# textdisplay.net
KiCad netlist of a schematic drawn in EAGLE
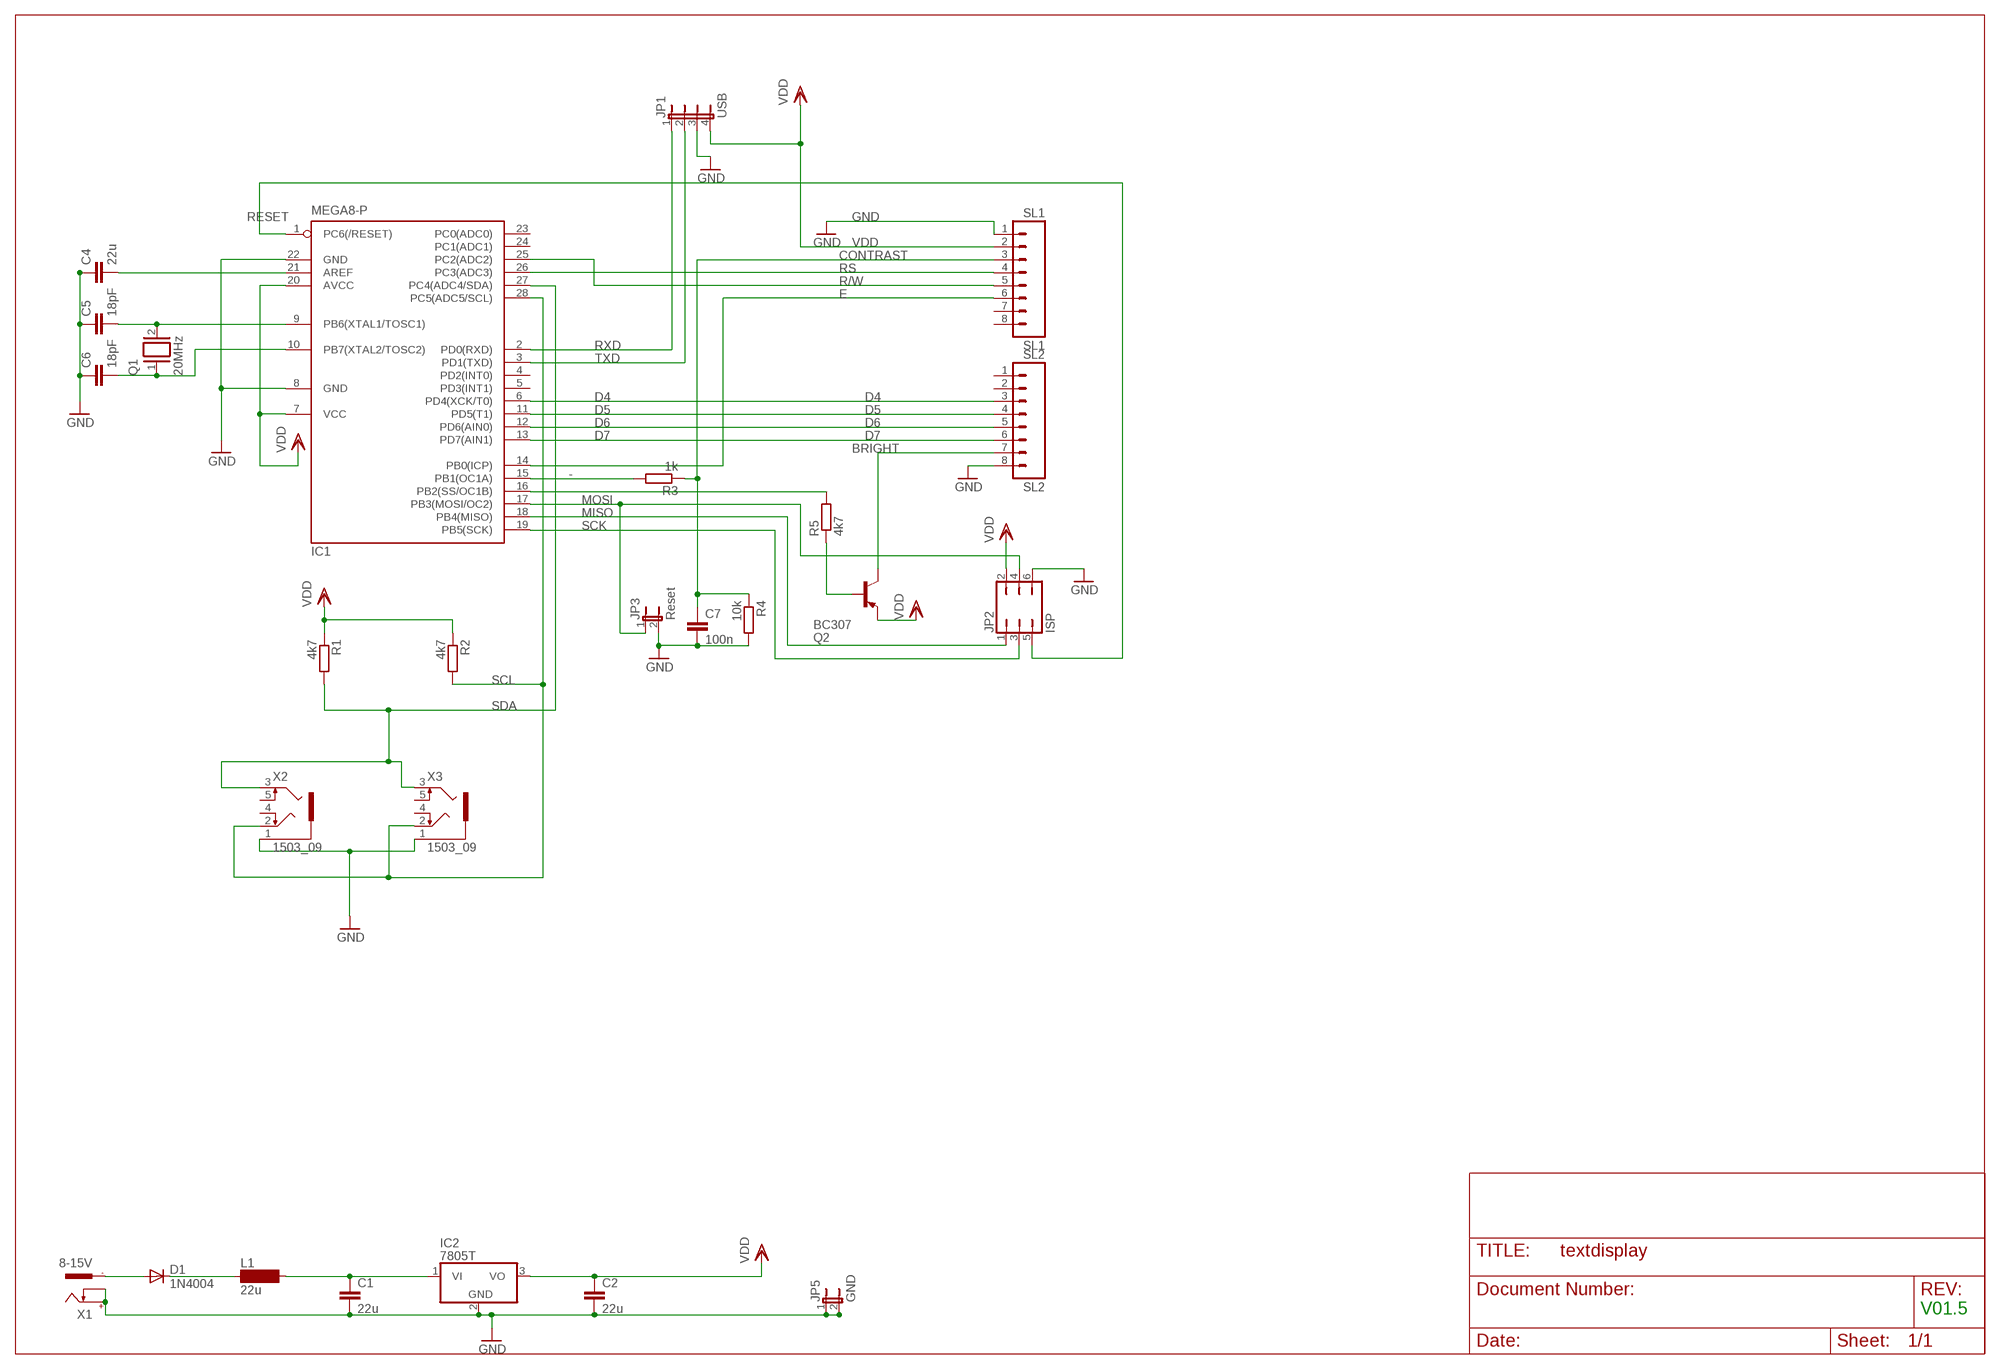
[diagram p0: schematic, sheet 1]

(export (version "E")
  (design (tool "Eeschema 10.0.6"))
  (components
    (comp (ref "C1")
      (value "22u")
      (footprint "eagle-import:C1206")
      (libsource (lib "eagle-import") (part "C-EUC1206"))
    )
    (comp (ref "C2")
      (value "22u")
      (footprint "eagle-import:C1206")
      (libsource (lib "eagle-import") (part "C-EUC1206"))
    )
    (comp (ref "C4")
      (value "22u")
      (footprint "eagle-import:C1206")
      (libsource (lib "eagle-import") (part "C-EUC1206"))
    )
    (comp (ref "C5")
      (value "18pF")
      (footprint "eagle-import:C025-025X050")
      (libsource (lib "eagle-import") (part "C-EU025-025X050"))
    )
    (comp (ref "C6")
      (value "18pF")
      (footprint "eagle-import:C025-025X050")
      (libsource (lib "eagle-import") (part "C-EU025-025X050"))
    )
    (comp (ref "C7")
      (value "100n")
      (footprint "eagle-import:C050-025X075")
      (libsource (lib "eagle-import") (part "C-EU050-025X075"))
    )
    (comp (ref "D1")
      (value "1N4004")
      (footprint "eagle-import:DO41-10")
      (libsource (lib "eagle-import") (part "1N4004"))
    )
    (comp (ref "IC1")
      (value "MEGA8-P")
      (footprint "eagle-import:DIL28-3")
      (libsource (lib "eagle-import") (part "MEGA8-P"))
    )
    (comp (ref "IC2")
      (value "7805T")
      (footprint "eagle-import:TO220H")
      (libsource (lib "eagle-import") (part "78T05"))
    )
    (comp (ref "JP1")
      (value "USB")
      (footprint "eagle-import:JP4")
      (libsource (lib "eagle-import") (part "JP4E"))
    )
    (comp (ref "JP2")
      (value "ISP")
      (footprint "eagle-import:JP3Q")
      (libsource (lib "eagle-import") (part "JP3Q"))
    )
    (comp (ref "JP3")
      (value "Reset")
      (footprint "eagle-import:JP1")
      (libsource (lib "eagle-import") (part "JP1E"))
    )
    (comp (ref "JP5")
      (value "GND")
      (footprint "eagle-import:JP1")
      (libsource (lib "eagle-import") (part "JP1E"))
    )
    (comp (ref "L1")
      (value "22u")
      (footprint "eagle-import:MS85")
      (libsource (lib "eagle-import") (part "MS85"))
    )
    (comp (ref "Q1")
      (value "20MHz")
      (footprint "eagle-import:QS")
      (libsource (lib "eagle-import") (part "XTAL/S"))
    )
    (comp (ref "Q2")
      (value "BC307")
      (footprint "eagle-import:TO92")
      (libsource (lib "eagle-import") (part "BC307"))
    )
    (comp (ref "R1")
      (value "4k7")
      (footprint "eagle-import:0207_2V")
      (libsource (lib "eagle-import") (part "R-EU_0207/2V"))
    )
    (comp (ref "R2")
      (value "4k7")
      (footprint "eagle-import:0207_2V")
      (libsource (lib "eagle-import") (part "R-EU_0207/2V"))
    )
    (comp (ref "R3")
      (value "1k")
      (footprint "eagle-import:0207_2V")
      (libsource (lib "eagle-import") (part "R-EU_0207/2V"))
    )
    (comp (ref "R4")
      (value "10k")
      (footprint "eagle-import:0207_2V")
      (libsource (lib "eagle-import") (part "R-EU_0207/2V"))
    )
    (comp (ref "R5")
      (value "4k7")
      (footprint "eagle-import:0207_2V")
      (libsource (lib "eagle-import") (part "R-EU_0207/2V"))
    )
    (comp (ref "SL1")
      (value "SL1")
      (footprint "eagle-import:08P")
      (libsource (lib "eagle-import") (part "M08"))
    )
    (comp (ref "SL2")
      (value "SL2")
      (footprint "eagle-import:08P")
      (libsource (lib "eagle-import") (part "M08"))
    )
    (comp (ref "X1")
      (value "8-15V")
      (footprint "eagle-import:737992-5")
      (libsource (lib "eagle-import") (part "737992-55"))
    )
    (comp (ref "X2")
      (value "1503_09")
      (footprint "eagle-import:1503_09")
      (libsource (lib "eagle-import") (part "1503_09"))
    )
    (comp (ref "X3")
      (value "1503_09")
      (footprint "eagle-import:1503_09")
      (libsource (lib "eagle-import") (part "1503_09"))
    )
  )
  (nets
    (net (code "1") (name "/-") (class "Default")
      (node (ref "IC1") (pin "15") (pinfunction "PB1(OC1A)_15") (pintype "bidirectional"))
      (node (ref "R3") (pin "2") (pinfunction "2_2") (pintype "passive"))
    )
    (net (code "2") (name "/BRIGHT") (class "Default")
      (node (ref "Q2") (pin "3") (pinfunction "C_3") (pintype "passive"))
      (node (ref "SL2") (pin "7") (pinfunction "7_7") (pintype "passive"))
    )
    (net (code "3") (name "/CONTRAST") (class "Default")
      (node (ref "C7") (pin "1") (pinfunction "1_1") (pintype "passive"))
      (node (ref "R3") (pin "1") (pinfunction "1_1") (pintype "passive"))
      (node (ref "R4") (pin "1") (pinfunction "1_1") (pintype "passive"))
      (node (ref "SL1") (pin "3") (pinfunction "3_3") (pintype "passive"))
    )
    (net (code "4") (name "/D4") (class "Default")
      (node (ref "IC1") (pin "6") (pinfunction "PD4(XCK/T0)_6") (pintype "bidirectional"))
      (node (ref "SL2") (pin "3") (pinfunction "3_3") (pintype "passive"))
    )
    (net (code "5") (name "/D5") (class "Default")
      (node (ref "IC1") (pin "11") (pinfunction "PD5(T1)_11") (pintype "bidirectional"))
      (node (ref "SL2") (pin "4") (pinfunction "4_4") (pintype "passive"))
    )
    (net (code "6") (name "/D6") (class "Default")
      (node (ref "IC1") (pin "12") (pinfunction "PD6(AIN0)_12") (pintype "bidirectional"))
      (node (ref "SL2") (pin "5") (pinfunction "5_5") (pintype "passive"))
    )
    (net (code "7") (name "/D7") (class "Default")
      (node (ref "IC1") (pin "13") (pinfunction "PD7(AIN1)_13") (pintype "bidirectional"))
      (node (ref "SL2") (pin "6") (pinfunction "6_6") (pintype "passive"))
    )
    (net (code "8") (name "/E") (class "Default")
      (node (ref "IC1") (pin "14") (pinfunction "PB0(ICP)_14") (pintype "bidirectional"))
      (node (ref "SL1") (pin "6") (pinfunction "6_6") (pintype "passive"))
    )
    (net (code "9") (name "/MISO") (class "Default")
      (node (ref "IC1") (pin "18") (pinfunction "PB4(MISO)_18") (pintype "bidirectional"))
      (node (ref "JP2") (pin "1") (pinfunction "1_1") (pintype "passive"))
    )
    (net (code "10") (name "/MOSI") (class "Default")
      (node (ref "IC1") (pin "17") (pinfunction "PB3(MOSI/OC2)_17") (pintype "bidirectional"))
      (node (ref "JP2") (pin "4") (pinfunction "4_4") (pintype "passive"))
      (node (ref "JP3") (pin "1") (pinfunction "1_1") (pintype "passive"))
    )
    (net (code "11") (name "/RESET") (class "Default")
      (node (ref "IC1") (pin "1") (pinfunction "PC6(/RESET)_1") (pintype "bidirectional"))
      (node (ref "JP2") (pin "5") (pinfunction "5_5") (pintype "passive"))
    )
    (net (code "12") (name "/RS") (class "Default")
      (node (ref "IC1") (pin "26") (pinfunction "PC3(ADC3)_26") (pintype "bidirectional"))
      (node (ref "SL1") (pin "4") (pinfunction "4_4") (pintype "passive"))
    )
    (net (code "13") (name "/RXD") (class "Default")
      (node (ref "IC1") (pin "2") (pinfunction "PD0(RXD)_2") (pintype "bidirectional"))
      (node (ref "JP1") (pin "1") (pinfunction "1_1") (pintype "passive"))
    )
    (net (code "14") (name "/R{slash}W") (class "Default")
      (node (ref "IC1") (pin "25") (pinfunction "PC2(ADC2)_25") (pintype "bidirectional"))
      (node (ref "SL1") (pin "5") (pinfunction "5_5") (pintype "passive"))
    )
    (net (code "15") (name "/SCK") (class "Default")
      (node (ref "IC1") (pin "19") (pinfunction "PB5(SCK)_19") (pintype "bidirectional"))
      (node (ref "JP2") (pin "3") (pinfunction "3_3") (pintype "passive"))
    )
    (net (code "16") (name "/SCL") (class "Default")
      (node (ref "IC1") (pin "28") (pinfunction "PC5(ADC5/SCL)_28") (pintype "bidirectional"))
      (node (ref "R2") (pin "2") (pinfunction "2_2") (pintype "passive"))
      (node (ref "X2") (pin "2") (pinfunction "2_2") (pintype "passive"))
      (node (ref "X3") (pin "2") (pinfunction "2_2") (pintype "passive"))
    )
    (net (code "17") (name "/SDA") (class "Default")
      (node (ref "IC1") (pin "27") (pinfunction "PC4(ADC4/SDA)_27") (pintype "bidirectional"))
      (node (ref "R1") (pin "2") (pinfunction "2_2") (pintype "passive"))
      (node (ref "X2") (pin "3") (pinfunction "3_3") (pintype "passive"))
      (node (ref "X3") (pin "3") (pinfunction "3_3") (pintype "passive"))
    )
    (net (code "18") (name "/TXD") (class "Default")
      (node (ref "IC1") (pin "3") (pinfunction "PD1(TXD)_3") (pintype "bidirectional"))
      (node (ref "JP1") (pin "2") (pinfunction "2_2") (pintype "passive"))
    )
    (net (code "19") (name "GND") (class "Default")
      (node (ref "C1") (pin "2") (pinfunction "2_2") (pintype "passive"))
      (node (ref "C2") (pin "2") (pinfunction "2_2") (pintype "passive"))
      (node (ref "C4") (pin "1") (pinfunction "1_1") (pintype "passive"))
      (node (ref "C5") (pin "1") (pinfunction "1_1") (pintype "passive"))
      (node (ref "C6") (pin "1") (pinfunction "1_1") (pintype "passive"))
      (node (ref "C7") (pin "2") (pinfunction "2_2") (pintype "passive"))
      (node (ref "IC1") (pin "22") (pinfunction "GND_22") (pintype "power_in"))
      (node (ref "IC1") (pin "8") (pinfunction "GND_8") (pintype "power_in"))
      (node (ref "IC2") (pin "2") (pinfunction "GND_2") (pintype "passive"))
      (node (ref "JP1") (pin "3") (pinfunction "3_3") (pintype "passive"))
      (node (ref "JP2") (pin "6") (pinfunction "6_6") (pintype "passive"))
      (node (ref "JP3") (pin "2") (pinfunction "2_2") (pintype "passive"))
      (node (ref "JP5") (pin "1") (pinfunction "1_1") (pintype "passive"))
      (node (ref "JP5") (pin "2") (pinfunction "2_2") (pintype "passive"))
      (node (ref "R4") (pin "2") (pinfunction "2_2") (pintype "passive"))
      (node (ref "SL1") (pin "1") (pinfunction "1_1") (pintype "passive"))
      (node (ref "SL2") (pin "8") (pinfunction "8_8") (pintype "passive"))
      (node (ref "X1") (pin "+") (pinfunction "+_+") (pintype "passive"))
      (node (ref "X1") (pin "K") (pinfunction "K_K") (pintype "passive"))
      (node (ref "X2") (pin "1") (pinfunction "1_1") (pintype "passive"))
      (node (ref "X3") (pin "1") (pinfunction "1_1") (pintype "passive"))
    )
    (net (code "20") (name "Net-(D1-PadA)") (class "Default")
      (node (ref "D1") (pin "A") (pinfunction "A_A") (pintype "passive"))
      (node (ref "X1") (pin "-1") (pinfunction "-1_-1") (pintype "passive"))
    )
    (net (code "21") (name "Net-(D1-PadC)") (class "Default")
      (node (ref "D1") (pin "C") (pinfunction "C_C") (pintype "passive"))
      (node (ref "L1") (pin "1") (pinfunction "1_1") (pintype "passive"))
    )
    (net (code "22") (name "Net-(IC1-AREF)") (class "Default")
      (node (ref "C4") (pin "2") (pinfunction "2_2") (pintype "passive"))
      (node (ref "IC1") (pin "21") (pinfunction "AREF_21") (pintype "passive"))
    )
    (net (code "23") (name "Net-(IC1-PB2(SS{slash}OC1B))") (class "Default")
      (node (ref "IC1") (pin "16") (pinfunction "PB2(SS/OC1B)_16") (pintype "bidirectional"))
      (node (ref "R5") (pin "2") (pinfunction "2_2") (pintype "passive"))
    )
    (net (code "24") (name "Net-(IC1-PB6(XTAL1{slash}TOSC1))") (class "Default")
      (node (ref "C5") (pin "2") (pinfunction "2_2") (pintype "passive"))
      (node (ref "IC1") (pin "9") (pinfunction "PB6(XTAL1/TOSC1)_9") (pintype "bidirectional"))
      (node (ref "Q1") (pin "2") (pinfunction "2_2") (pintype "passive"))
    )
    (net (code "25") (name "Net-(IC1-PB7(XTAL2{slash}TOSC2))") (class "Default")
      (node (ref "C6") (pin "2") (pinfunction "2_2") (pintype "passive"))
      (node (ref "IC1") (pin "10") (pinfunction "PB7(XTAL2/TOSC2)_10") (pintype "bidirectional"))
      (node (ref "Q1") (pin "1") (pinfunction "1_1") (pintype "passive"))
    )
    (net (code "26") (name "Net-(IC2-VI)") (class "Default")
      (node (ref "C1") (pin "1") (pinfunction "1_1") (pintype "passive"))
      (node (ref "IC2") (pin "1") (pinfunction "VI_1") (pintype "input"))
      (node (ref "L1") (pin "2") (pinfunction "2_2") (pintype "passive"))
    )
    (net (code "27") (name "Net-(Q2-B)") (class "Default")
      (node (ref "Q2") (pin "2") (pinfunction "B_2") (pintype "passive"))
      (node (ref "R5") (pin "1") (pinfunction "1_1") (pintype "passive"))
    )
    (net (code "28") (name "VDD") (class "Default")
      (node (ref "C2") (pin "1") (pinfunction "1_1") (pintype "passive"))
      (node (ref "IC1") (pin "20") (pinfunction "AVCC_20") (pintype "power_in"))
      (node (ref "IC1") (pin "7") (pinfunction "VCC_7") (pintype "power_in"))
      (node (ref "IC2") (pin "3") (pinfunction "VO_3") (pintype "passive"))
      (node (ref "JP1") (pin "4") (pinfunction "4_4") (pintype "passive"))
      (node (ref "JP2") (pin "2") (pinfunction "2_2") (pintype "passive"))
      (node (ref "Q2") (pin "1") (pinfunction "E_1") (pintype "passive"))
      (node (ref "R1") (pin "1") (pinfunction "1_1") (pintype "passive"))
      (node (ref "R2") (pin "1") (pinfunction "1_1") (pintype "passive"))
      (node (ref "SL1") (pin "2") (pinfunction "2_2") (pintype "passive"))
    )
    (net (code "29") (name "unconnected-(IC1-PC0(ADC0)-Pad23)") (class "Default")
      (node (ref "IC1") (pin "23") (pinfunction "PC0(ADC0)_23") (pintype "bidirectional"))
    )
    (net (code "30") (name "unconnected-(IC1-PC1(ADC1)-Pad24)") (class "Default")
      (node (ref "IC1") (pin "24") (pinfunction "PC1(ADC1)_24") (pintype "bidirectional"))
    )
    (net (code "31") (name "unconnected-(IC1-PD2(INT0)-Pad4)") (class "Default")
      (node (ref "IC1") (pin "4") (pinfunction "PD2(INT0)_4") (pintype "bidirectional"))
    )
    (net (code "32") (name "unconnected-(IC1-PD3(INT1)-Pad5)") (class "Default")
      (node (ref "IC1") (pin "5") (pinfunction "PD3(INT1)_5") (pintype "bidirectional"))
    )
    (net (code "33") (name "unconnected-(SL1-Pad7)") (class "Default")
      (node (ref "SL1") (pin "7") (pinfunction "7_7") (pintype "passive"))
    )
    (net (code "34") (name "unconnected-(SL1-Pad8)") (class "Default")
      (node (ref "SL1") (pin "8") (pinfunction "8_8") (pintype "passive"))
    )
    (net (code "35") (name "unconnected-(SL2-Pad1)") (class "Default")
      (node (ref "SL2") (pin "1") (pinfunction "1_1") (pintype "passive"))
    )
    (net (code "36") (name "unconnected-(SL2-Pad2)") (class "Default")
      (node (ref "SL2") (pin "2") (pinfunction "2_2") (pintype "passive"))
    )
    (net (code "37") (name "unconnected-(X1-Pad-2)") (class "Default")
      (node (ref "X1") (pin "-2") (pinfunction "-2_-2") (pintype "passive"))
    )
    (net (code "38") (name "unconnected-(X2-Pad4)") (class "Default")
      (node (ref "X2") (pin "4") (pinfunction "4_4") (pintype "passive"))
    )
    (net (code "39") (name "unconnected-(X2-Pad5)") (class "Default")
      (node (ref "X2") (pin "5") (pinfunction "5_5") (pintype "passive"))
    )
    (net (code "40") (name "unconnected-(X3-Pad4)") (class "Default")
      (node (ref "X3") (pin "4") (pinfunction "4_4") (pintype "passive"))
    )
    (net (code "41") (name "unconnected-(X3-Pad5)") (class "Default")
      (node (ref "X3") (pin "5") (pinfunction "5_5") (pintype "passive"))
    )
  )
)
